# Narrow_AAA_sensor_v2.net
KiCad netlist of a schematic drawn in EAGLE
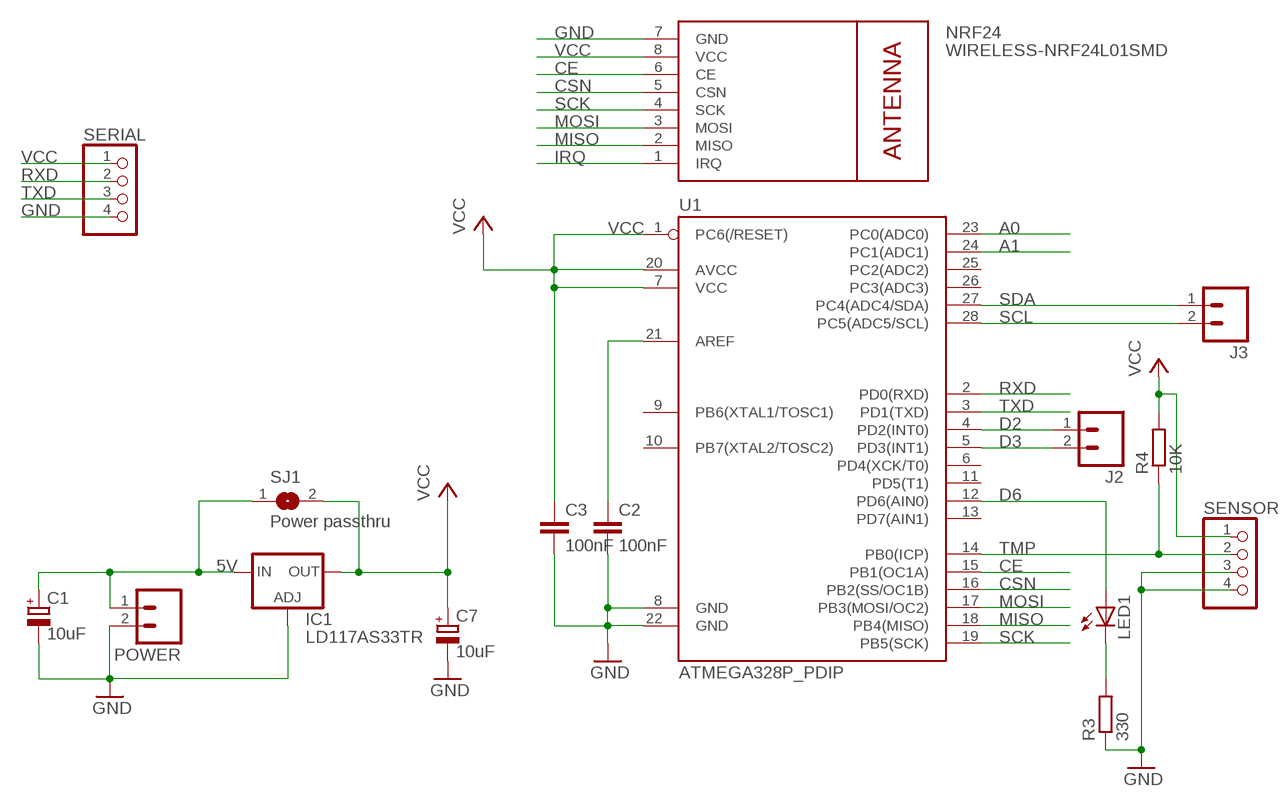
[diagram p0: schematic, sheet 1]

(export (version "E")
  (design (tool "Eeschema 10.0.6"))
  (components
    (comp (ref "C1")
      (value "10uF")
      (footprint "eagle-import:E2,5-5")
      (libsource (lib "eagle-import") (part "CPOL-EUE2.5-5"))
    )
    (comp (ref "C2")
      (value "100nF")
      (footprint "eagle-import:C025-025X050")
      (libsource (lib "eagle-import") (part "C-EU025-025X050"))
    )
    (comp (ref "C3")
      (value "100nF")
      (footprint "eagle-import:C025-025X050")
      (libsource (lib "eagle-import") (part "C-EU025-025X050"))
    )
    (comp (ref "C7")
      (value "10uF")
      (footprint "eagle-import:E2,5-5")
      (libsource (lib "eagle-import") (part "CPOL-EUE2.5-5"))
    )
    (comp (ref "IC1")
      (value "LD117AS33TR")
      (footprint "eagle-import:SOT223")
      (libsource (lib "eagle-import") (part "LD117A?S33TR"))
    )
    (comp (ref "J2")
      (value "M02PTH")
      (footprint "eagle-import:1X02")
      (libsource (lib "eagle-import") (part "M02PTH"))
    )
    (comp (ref "J3")
      (value "M021X02_NO_SILK")
      (footprint "eagle-import:1X02_NO_SILK")
      (libsource (lib "eagle-import") (part "M021X02_NO_SILK"))
    )
    (comp (ref "LED1")
      (value "LED3MM")
      (footprint "eagle-import:LED3MM")
      (libsource (lib "eagle-import") (part "LED3MM"))
    )
    (comp (ref "NRF24")
      (value "WIRELESS-NRF24L01SMD")
      (footprint "eagle-import:WIRELESS-NRF24L01-SMD")
      (libsource (lib "eagle-import") (part "WIRELESS-NRF24L01SMD"))
    )
    (comp (ref "POWER")
      (value "M021X02_NO_SILK")
      (footprint "eagle-import:1X02_NO_SILK")
      (libsource (lib "eagle-import") (part "M021X02_NO_SILK"))
    )
    (comp (ref "R3")
      (value "330")
      (footprint "eagle-import:0204_7")
      (libsource (lib "eagle-import") (part "R-EU_0204/7"))
    )
    (comp (ref "R4")
      (value "10K")
      (footprint "eagle-import:0204_7")
      (libsource (lib "eagle-import") (part "R-EU_0204/7"))
    )
    (comp (ref "SENSOR")
      (value "PINHD-1X4")
      (footprint "eagle-import:1X04")
      (libsource (lib "eagle-import") (part "PINHD-1X4"))
    )
    (comp (ref "SERIAL")
      (value "PINHD-1X4")
      (footprint "eagle-import:1X04")
      (libsource (lib "eagle-import") (part "PINHD-1X4"))
    )
    (comp (ref "SJ1")
      (value "Power passthru")
      (footprint "eagle-import:SJ")
      (libsource (lib "eagle-import") (part "SJ"))
    )
    (comp (ref "U1")
      (value "ATMEGA328P_PDIP")
      (footprint "eagle-import:DIL28-3")
      (libsource (lib "eagle-import") (part "ATMEGA328P_PDIP"))
    )
  )
  (nets
    (net (code "1") (name "/5V") (class "Default")
      (node (ref "C1") (pin "+") (pinfunction "+_+") (pintype "passive"))
      (node (ref "IC1") (pin "3") (pinfunction "IN_3") (pintype "input"))
      (node (ref "POWER") (pin "1") (pinfunction "1_1") (pintype "passive"))
      (node (ref "SJ1") (pin "1") (pinfunction "1_1") (pintype "passive"))
    )
    (net (code "2") (name "/A0") (class "Default")
      (node (ref "U1") (pin "23") (pinfunction "PC0(ADC0)_23") (pintype "bidirectional"))
    )
    (net (code "3") (name "/A1") (class "Default")
      (node (ref "U1") (pin "24") (pinfunction "PC1(ADC1)_24") (pintype "bidirectional"))
    )
    (net (code "4") (name "/CE") (class "Default")
      (node (ref "NRF24") (pin "6") (pinfunction "CE_6") (pintype "bidirectional"))
      (node (ref "U1") (pin "15") (pinfunction "PB1(OC1A)_15") (pintype "bidirectional"))
    )
    (net (code "5") (name "/CSN") (class "Default")
      (node (ref "NRF24") (pin "5") (pinfunction "CSN_5") (pintype "bidirectional"))
      (node (ref "U1") (pin "16") (pinfunction "PB2(SS/OC1B)_16") (pintype "bidirectional"))
    )
    (net (code "6") (name "/D2") (class "Default")
      (node (ref "J2") (pin "1") (pinfunction "1_1") (pintype "passive"))
      (node (ref "U1") (pin "4") (pinfunction "PD2(INT0)_4") (pintype "bidirectional"))
    )
    (net (code "7") (name "/D3") (class "Default")
      (node (ref "J2") (pin "2") (pinfunction "2_2") (pintype "passive"))
      (node (ref "U1") (pin "5") (pinfunction "PD3(INT1)_5") (pintype "bidirectional"))
    )
    (net (code "8") (name "/D6") (class "Default")
      (node (ref "LED1") (pin "A") (pinfunction "A_A") (pintype "passive"))
      (node (ref "U1") (pin "12") (pinfunction "PD6(AIN0)_12") (pintype "bidirectional"))
    )
    (net (code "9") (name "/IRQ") (class "Default")
      (node (ref "NRF24") (pin "1") (pinfunction "IRQ_1") (pintype "bidirectional"))
    )
    (net (code "10") (name "/MISO") (class "Default")
      (node (ref "NRF24") (pin "2") (pinfunction "MISO_2") (pintype "bidirectional"))
      (node (ref "U1") (pin "18") (pinfunction "PB4(MISO)_18") (pintype "bidirectional"))
    )
    (net (code "11") (name "/MOSI") (class "Default")
      (node (ref "NRF24") (pin "3") (pinfunction "MOSI_3") (pintype "bidirectional"))
      (node (ref "U1") (pin "17") (pinfunction "PB3(MOSI/OC2)_17") (pintype "bidirectional"))
    )
    (net (code "12") (name "/RXD") (class "Default")
      (node (ref "SERIAL") (pin "2") (pinfunction "2_2") (pintype "passive"))
      (node (ref "U1") (pin "2") (pinfunction "PD0(RXD)_2") (pintype "bidirectional"))
    )
    (net (code "13") (name "/SCK") (class "Default")
      (node (ref "NRF24") (pin "4") (pinfunction "SCK_4") (pintype "bidirectional"))
      (node (ref "U1") (pin "19") (pinfunction "PB5(SCK)_19") (pintype "bidirectional"))
    )
    (net (code "14") (name "/SCL") (class "Default")
      (node (ref "J3") (pin "2") (pinfunction "2_2") (pintype "passive"))
      (node (ref "U1") (pin "28") (pinfunction "PC5(ADC5/SCL)_28") (pintype "bidirectional"))
    )
    (net (code "15") (name "/SDA") (class "Default")
      (node (ref "J3") (pin "1") (pinfunction "1_1") (pintype "passive"))
      (node (ref "U1") (pin "27") (pinfunction "PC4(ADC4/SDA)_27") (pintype "bidirectional"))
    )
    (net (code "16") (name "/TMP") (class "Default")
      (node (ref "R4") (pin "1") (pinfunction "1_1") (pintype "passive"))
      (node (ref "SENSOR") (pin "2") (pinfunction "2_2") (pintype "passive"))
      (node (ref "U1") (pin "14") (pinfunction "PB0(ICP)_14") (pintype "bidirectional"))
    )
    (net (code "17") (name "/TXD") (class "Default")
      (node (ref "SERIAL") (pin "3") (pinfunction "3_3") (pintype "passive"))
      (node (ref "U1") (pin "3") (pinfunction "PD1(TXD)_3") (pintype "bidirectional"))
    )
    (net (code "18") (name "GND") (class "Default")
      (node (ref "C1") (pin "-") (pinfunction "-_-") (pintype "passive"))
      (node (ref "C2") (pin "2") (pinfunction "2_2") (pintype "passive"))
      (node (ref "C3") (pin "2") (pinfunction "2_2") (pintype "passive"))
      (node (ref "C7") (pin "-") (pinfunction "-_-") (pintype "passive"))
      (node (ref "IC1") (pin "1") (pinfunction "ADJ_1") (pintype "input"))
      (node (ref "NRF24") (pin "7") (pinfunction "GND_7") (pintype "power_in"))
      (node (ref "POWER") (pin "2") (pinfunction "2_2") (pintype "passive"))
      (node (ref "R3") (pin "1") (pinfunction "1_1") (pintype "passive"))
      (node (ref "SENSOR") (pin "3") (pinfunction "3_3") (pintype "passive"))
      (node (ref "SENSOR") (pin "4") (pinfunction "4_4") (pintype "passive"))
      (node (ref "SERIAL") (pin "4") (pinfunction "4_4") (pintype "passive"))
      (node (ref "U1") (pin "22") (pinfunction "GND_22") (pintype "bidirectional"))
      (node (ref "U1") (pin "8") (pinfunction "GND_8") (pintype "bidirectional"))
    )
    (net (code "19") (name "Net-(LED1-C)") (class "Default")
      (node (ref "LED1") (pin "K") (pinfunction "C_K") (pintype "passive"))
      (node (ref "R3") (pin "2") (pinfunction "2_2") (pintype "passive"))
    )
    (net (code "20") (name "Net-(U1-AREF)") (class "Default")
      (node (ref "C2") (pin "1") (pinfunction "1_1") (pintype "passive"))
      (node (ref "U1") (pin "21") (pinfunction "AREF_21") (pintype "bidirectional"))
    )
    (net (code "21") (name "VCC") (class "Default")
      (node (ref "C3") (pin "1") (pinfunction "1_1") (pintype "passive"))
      (node (ref "C7") (pin "+") (pinfunction "+_+") (pintype "passive"))
      (node (ref "IC1") (pin "4") (pinfunction "OUT_4") (pintype "passive"))
      (node (ref "NRF24") (pin "8") (pinfunction "VCC_8") (pintype "power_in"))
      (node (ref "R4") (pin "2") (pinfunction "2_2") (pintype "passive"))
      (node (ref "SENSOR") (pin "1") (pinfunction "1_1") (pintype "passive"))
      (node (ref "SERIAL") (pin "1") (pinfunction "1_1") (pintype "passive"))
      (node (ref "SJ1") (pin "2") (pinfunction "2_2") (pintype "passive"))
      (node (ref "U1") (pin "1") (pinfunction "PC6(/RESET)_1") (pintype "bidirectional"))
      (node (ref "U1") (pin "20") (pinfunction "AVCC_20") (pintype "bidirectional"))
      (node (ref "U1") (pin "7") (pinfunction "VCC_7") (pintype "bidirectional"))
    )
    (net (code "22") (name "unconnected-(U1-PB6(XTAL1{slash}TOSC1)-Pad9)") (class "Default")
      (node (ref "U1") (pin "9") (pinfunction "PB6(XTAL1/TOSC1)_9") (pintype "bidirectional"))
    )
    (net (code "23") (name "unconnected-(U1-PB7(XTAL2{slash}TOSC2)-Pad10)") (class "Default")
      (node (ref "U1") (pin "10") (pinfunction "PB7(XTAL2/TOSC2)_10") (pintype "bidirectional"))
    )
    (net (code "24") (name "unconnected-(U1-PC2(ADC2)-Pad25)") (class "Default")
      (node (ref "U1") (pin "25") (pinfunction "PC2(ADC2)_25") (pintype "bidirectional"))
    )
    (net (code "25") (name "unconnected-(U1-PC3(ADC3)-Pad26)") (class "Default")
      (node (ref "U1") (pin "26") (pinfunction "PC3(ADC3)_26") (pintype "bidirectional"))
    )
    (net (code "26") (name "unconnected-(U1-PD4(XCK{slash}T0)-Pad6)") (class "Default")
      (node (ref "U1") (pin "6") (pinfunction "PD4(XCK/T0)_6") (pintype "bidirectional"))
    )
    (net (code "27") (name "unconnected-(U1-PD5(T1)-Pad11)") (class "Default")
      (node (ref "U1") (pin "11") (pinfunction "PD5(T1)_11") (pintype "bidirectional"))
    )
    (net (code "28") (name "unconnected-(U1-PD7(AIN1)-Pad13)") (class "Default")
      (node (ref "U1") (pin "13") (pinfunction "PD7(AIN1)_13") (pintype "bidirectional"))
    )
  )
)
